# oscillograph.net
KiCad netlist of a schematic drawn in Altium Designer
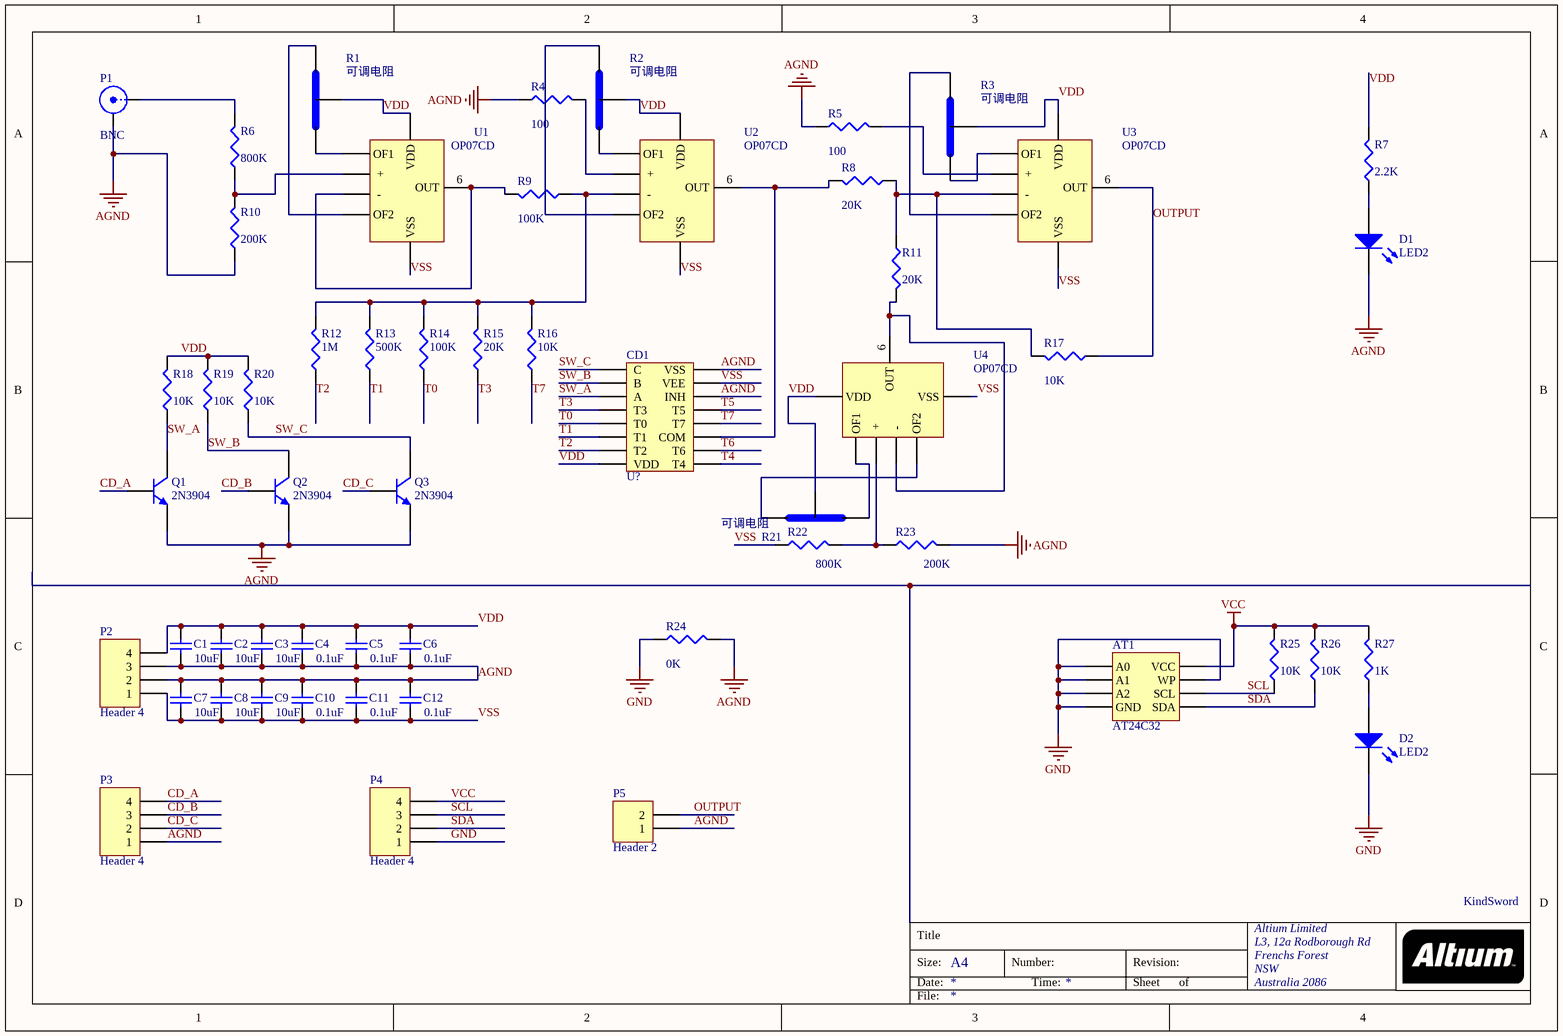
[diagram p0: oscillograph.SchDoc]

(export (version "E")
  (design (tool "Eeschema 10.0.6"))
  (components
    (comp (ref "AT1") (value "AT24C32") (footprint "AT24") (libsource (lib "AD元件库") (part "AT24C32")))
    (comp (ref "C1")
      (value "10uF")
      (footprint "1608[0603]")
      (description "Capacitor (Semiconductor SIM Model)")
      (fields (field (name "Comment") "Cap Semi") (field (name "PUBLISHER") "Altium Limited"))
      (libsource (lib "Miscellaneous Devices") (part "Cap Semi"))
    )
    (comp (ref "C2")
      (value "10uF")
      (footprint "1608[0603]")
      (description "Capacitor (Semiconductor SIM Model)")
      (fields (field (name "Comment") "Cap Semi") (field (name "PUBLISHER") "Altium Limited"))
      (libsource (lib "Miscellaneous Devices") (part "Cap Semi"))
    )
    (comp (ref "C3")
      (value "10uF")
      (footprint "1608[0603]")
      (description "Capacitor (Semiconductor SIM Model)")
      (fields (field (name "Comment") "Cap Semi") (field (name "PUBLISHER") "Altium Limited"))
      (libsource (lib "Miscellaneous Devices") (part "Cap Semi"))
    )
    (comp (ref "C4")
      (value "0.1uF")
      (footprint "1608[0603]")
      (description "Capacitor (Semiconductor SIM Model)")
      (fields (field (name "Comment") "Cap Semi") (field (name "PUBLISHER") "Altium Limited"))
      (libsource (lib "Miscellaneous Devices") (part "Cap Semi"))
    )
    (comp (ref "C5")
      (value "0.1uF")
      (footprint "1608[0603]")
      (description "Capacitor (Semiconductor SIM Model)")
      (fields (field (name "Comment") "Cap Semi") (field (name "PUBLISHER") "Altium Limited"))
      (libsource (lib "Miscellaneous Devices") (part "Cap Semi"))
    )
    (comp (ref "C6")
      (value "0.1uF")
      (footprint "1608[0603]")
      (description "Capacitor (Semiconductor SIM Model)")
      (fields (field (name "Comment") "Cap Semi") (field (name "PUBLISHER") "Altium Limited"))
      (libsource (lib "Miscellaneous Devices") (part "Cap Semi"))
    )
    (comp (ref "C7")
      (value "10uF")
      (footprint "1608[0603]")
      (description "Capacitor (Semiconductor SIM Model)")
      (fields (field (name "Comment") "Cap Semi") (field (name "PUBLISHER") "Altium Limited"))
      (libsource (lib "Miscellaneous Devices") (part "Cap Semi"))
    )
    (comp (ref "C8")
      (value "10uF")
      (footprint "1608[0603]")
      (description "Capacitor (Semiconductor SIM Model)")
      (fields (field (name "Comment") "Cap Semi") (field (name "PUBLISHER") "Altium Limited"))
      (libsource (lib "Miscellaneous Devices") (part "Cap Semi"))
    )
    (comp (ref "C9")
      (value "10uF")
      (footprint "1608[0603]")
      (description "Capacitor (Semiconductor SIM Model)")
      (fields (field (name "Comment") "Cap Semi") (field (name "PUBLISHER") "Altium Limited"))
      (libsource (lib "Miscellaneous Devices") (part "Cap Semi"))
    )
    (comp (ref "C10")
      (value "0.1uF")
      (footprint "1608[0603]")
      (description "Capacitor (Semiconductor SIM Model)")
      (fields (field (name "Comment") "Cap Semi") (field (name "PUBLISHER") "Altium Limited"))
      (libsource (lib "Miscellaneous Devices") (part "Cap Semi"))
    )
    (comp (ref "C11")
      (value "0.1uF")
      (footprint "1608[0603]")
      (description "Capacitor (Semiconductor SIM Model)")
      (fields (field (name "Comment") "Cap Semi") (field (name "PUBLISHER") "Altium Limited"))
      (libsource (lib "Miscellaneous Devices") (part "Cap Semi"))
    )
    (comp (ref "C12")
      (value "0.1uF")
      (footprint "1608[0603]")
      (description "Capacitor (Semiconductor SIM Model)")
      (fields (field (name "Comment") "Cap Semi") (field (name "PUBLISHER") "Altium Limited"))
      (libsource (lib "Miscellaneous Devices") (part "Cap Semi"))
    )
    (comp (ref "CD1")
      (value "U?")
      (footprint "cd4051")
      (description "CD4051")
      (libsource (lib "AD元件库") (part "CD4051B"))
    )
    (comp (ref "D1")
      (value "LED2")
      (footprint "3.2X1.6X1.1")
      (description "Typical RED, GREEN, YELLOW, AMBER GaAs LED")
      (fields (field (name "PUBLISHER") "Altium Limited"))
      (libsource (lib "Miscellaneous Devices") (part "LED2"))
    )
    (comp (ref "D2")
      (value "LED2")
      (footprint "3.2X1.6X1.1")
      (description "Typical RED, GREEN, YELLOW, AMBER GaAs LED")
      (fields (field (name "PUBLISHER") "Altium Limited"))
      (libsource (lib "Miscellaneous Devices") (part "LED2"))
    )
    (comp (ref "Logo1")
      (value "~")
      (footprint "logo")
      (description "L?")
      (libsource (lib "AD元件库") (part "logo"))
    )
    (comp (ref "P1")
      (value "BNC")
      (footprint "BNC_RA CON")
      (description "BNC Elbow Connector")
      (fields (field (name "PUBLISHER") "Altium Limited"))
      (libsource (lib "Miscellaneous Connectors") (part "BNC"))
    )
    (comp (ref "P2")
      (value "Header 4")
      (footprint "HDR1X4")
      (description "Header, 4-Pin")
      (fields (field (name "PUBLISHER") "Altium Limited"))
      (libsource (lib "Miscellaneous Connectors") (part "Header 4"))
    )
    (comp (ref "P3")
      (value "Header 4")
      (footprint "HDR1X4")
      (description "Header, 4-Pin")
      (fields (field (name "PUBLISHER") "Altium Limited"))
      (libsource (lib "Miscellaneous Connectors") (part "Header 4"))
    )
    (comp (ref "P4")
      (value "Header 4")
      (footprint "HDR1X4")
      (description "Header, 4-Pin")
      (fields (field (name "PUBLISHER") "Altium Limited"))
      (libsource (lib "Miscellaneous Connectors") (part "Header 4"))
    )
    (comp (ref "P5")
      (value "Header 2")
      (footprint "HDR1X2")
      (description "Header, 2-Pin")
      (fields (field (name "PUBLISHER") "Altium Limited"))
      (libsource (lib "Miscellaneous Connectors") (part "Header 2"))
    )
    (comp (ref "Q1")
      (value "2N3904")
      (footprint "TO-92A")
      (description "NPN General Purpose Amplifier")
      (fields (field (name "PUBLISHER") "Altium Limited"))
      (libsource (lib "Miscellaneous Devices") (part "2N3904"))
    )
    (comp (ref "Q2")
      (value "2N3904")
      (footprint "TO-92A")
      (description "NPN General Purpose Amplifier")
      (fields (field (name "PUBLISHER") "Altium Limited"))
      (libsource (lib "Miscellaneous Devices") (part "2N3904"))
    )
    (comp (ref "Q3")
      (value "2N3904")
      (footprint "TO-92A")
      (description "NPN General Purpose Amplifier")
      (fields (field (name "PUBLISHER") "Altium Limited"))
      (libsource (lib "Miscellaneous Devices") (part "2N3904"))
    )
    (comp (ref "R1")
      (value "可调电阻")
      (footprint "3296可调电阻")
      (description "R?")
      (libsource (lib "AD元件库") (part "3296可调电阻"))
    )
    (comp (ref "R2")
      (value "可调电阻")
      (footprint "3296可调电阻")
      (description "R?")
      (libsource (lib "AD元件库") (part "3296可调电阻"))
    )
    (comp (ref "R3")
      (value "可调电阻")
      (footprint "3296可调电阻")
      (description "R?")
      (libsource (lib "AD元件库") (part "3296可调电阻"))
    )
    (comp (ref "R4")
      (value "100")
      (footprint "J1-0603")
      (description "Resistor")
      (fields (field (name "Comment") "Res3") (field (name "PUBLISHER") "Altium Limited"))
      (libsource (lib "Miscellaneous Devices") (part "Res3"))
    )
    (comp (ref "R5")
      (value "100")
      (footprint "J1-0603")
      (description "Resistor")
      (fields (field (name "Comment") "Res3") (field (name "PUBLISHER") "Altium Limited"))
      (libsource (lib "Miscellaneous Devices") (part "Res3"))
    )
    (comp (ref "R6")
      (value "800K")
      (footprint "J1-0603")
      (description "Resistor")
      (fields (field (name "Comment") "Res3") (field (name "PUBLISHER") "Altium Limited"))
      (libsource (lib "Miscellaneous Devices") (part "Res3"))
    )
    (comp (ref "R7")
      (value "2.2K")
      (footprint "J1-0603")
      (description "Resistor")
      (fields (field (name "Comment") "Res3") (field (name "PUBLISHER") "Altium Limited"))
      (libsource (lib "Miscellaneous Devices") (part "Res3"))
    )
    (comp (ref "R8")
      (value "20K")
      (footprint "J1-0603")
      (description "Resistor")
      (fields (field (name "Comment") "Res3") (field (name "PUBLISHER") "Altium Limited"))
      (libsource (lib "Miscellaneous Devices") (part "Res3"))
    )
    (comp (ref "R9")
      (value "100K")
      (footprint "J1-0603")
      (description "Resistor")
      (fields (field (name "Comment") "Res3") (field (name "PUBLISHER") "Altium Limited"))
      (libsource (lib "Miscellaneous Devices") (part "Res3"))
    )
    (comp (ref "R10")
      (value "200K")
      (footprint "J1-0603")
      (description "Resistor")
      (fields (field (name "Comment") "Res3") (field (name "PUBLISHER") "Altium Limited"))
      (libsource (lib "Miscellaneous Devices") (part "Res3"))
    )
    (comp (ref "R11")
      (value "20K")
      (footprint "J1-0603")
      (description "Resistor")
      (fields (field (name "Comment") "Res3") (field (name "PUBLISHER") "Altium Limited"))
      (libsource (lib "Miscellaneous Devices") (part "Res3"))
    )
    (comp (ref "R12")
      (value "1M")
      (footprint "J1-0603")
      (description "Resistor")
      (fields (field (name "Comment") "Res3") (field (name "PUBLISHER") "Altium Limited"))
      (libsource (lib "Miscellaneous Devices") (part "Res3"))
    )
    (comp (ref "R13")
      (value "500K")
      (footprint "J1-0603")
      (description "Resistor")
      (fields (field (name "Comment") "Res3") (field (name "PUBLISHER") "Altium Limited"))
      (libsource (lib "Miscellaneous Devices") (part "Res3"))
    )
    (comp (ref "R14")
      (value "100K")
      (footprint "J1-0603")
      (description "Resistor")
      (fields (field (name "Comment") "Res3") (field (name "PUBLISHER") "Altium Limited"))
      (libsource (lib "Miscellaneous Devices") (part "Res3"))
    )
    (comp (ref "R15")
      (value "20K")
      (footprint "J1-0603")
      (description "Resistor")
      (fields (field (name "Comment") "Res3") (field (name "PUBLISHER") "Altium Limited"))
      (libsource (lib "Miscellaneous Devices") (part "Res3"))
    )
    (comp (ref "R16")
      (value "10K")
      (footprint "J1-0603")
      (description "Resistor")
      (fields (field (name "Comment") "Res3") (field (name "PUBLISHER") "Altium Limited"))
      (libsource (lib "Miscellaneous Devices") (part "Res3"))
    )
    (comp (ref "R17")
      (value "10K")
      (footprint "J1-0603")
      (description "Resistor")
      (fields (field (name "Comment") "Res3") (field (name "PUBLISHER") "Altium Limited"))
      (libsource (lib "Miscellaneous Devices") (part "Res3"))
    )
    (comp (ref "R18")
      (value "10K")
      (footprint "J1-0603")
      (description "Resistor")
      (fields (field (name "Comment") "Res3") (field (name "PUBLISHER") "Altium Limited"))
      (libsource (lib "Miscellaneous Devices") (part "Res3"))
    )
    (comp (ref "R19")
      (value "10K")
      (footprint "J1-0603")
      (description "Resistor")
      (fields (field (name "Comment") "Res3") (field (name "PUBLISHER") "Altium Limited"))
      (libsource (lib "Miscellaneous Devices") (part "Res3"))
    )
    (comp (ref "R20")
      (value "10K")
      (footprint "J1-0603")
      (description "Resistor")
      (fields (field (name "Comment") "Res3") (field (name "PUBLISHER") "Altium Limited"))
      (libsource (lib "Miscellaneous Devices") (part "Res3"))
    )
    (comp (ref "R21")
      (value "可调电阻")
      (footprint "3296可调电阻")
      (description "R?")
      (libsource (lib "AD元件库") (part "3296可调电阻"))
    )
    (comp (ref "R22")
      (value "800K")
      (footprint "J1-0603")
      (description "Resistor")
      (fields (field (name "Comment") "Res3") (field (name "PUBLISHER") "Altium Limited"))
      (libsource (lib "Miscellaneous Devices") (part "Res3"))
    )
    (comp (ref "R23")
      (value "200K")
      (footprint "J1-0603")
      (description "Resistor")
      (fields (field (name "Comment") "Res3") (field (name "PUBLISHER") "Altium Limited"))
      (libsource (lib "Miscellaneous Devices") (part "Res3"))
    )
    (comp (ref "R24")
      (value "0K")
      (footprint "J1-0603")
      (description "Resistor")
      (fields (field (name "Comment") "Res3") (field (name "PUBLISHER") "Altium Limited"))
      (libsource (lib "Miscellaneous Devices") (part "Res3"))
    )
    (comp (ref "R25")
      (value "10K")
      (footprint "J1-0603")
      (description "Resistor")
      (fields (field (name "Comment") "Res3") (field (name "PUBLISHER") "Altium Limited"))
      (libsource (lib "Miscellaneous Devices") (part "Res3"))
    )
    (comp (ref "R26")
      (value "10K")
      (footprint "J1-0603")
      (description "Resistor")
      (fields (field (name "Comment") "Res3") (field (name "PUBLISHER") "Altium Limited"))
      (libsource (lib "Miscellaneous Devices") (part "Res3"))
    )
    (comp (ref "R27")
      (value "1K")
      (footprint "J1-0603")
      (description "Resistor")
      (fields (field (name "Comment") "Res3") (field (name "PUBLISHER") "Altium Limited"))
      (libsource (lib "Miscellaneous Devices") (part "Res3"))
    )
    (comp (ref "U1") (value "OP07CD") (footprint "OP07C") (libsource (lib "AD元件库") (part "OP07CD")))
    (comp (ref "U2") (value "OP07CD") (footprint "OP07C") (libsource (lib "AD元件库") (part "OP07CD")))
    (comp (ref "U3") (value "OP07CD") (footprint "OP07C") (libsource (lib "AD元件库") (part "OP07CD")))
    (comp (ref "U4") (value "OP07CD") (footprint "OP07C") (libsource (lib "") (part "OP07CD_1")))
  )
  (nets
    (net (code "1") (name "/CD_A") (class "Default")
      (node (ref "P3") (pin "4") (pinfunction "4_4") (pintype "passive"))
      (node (ref "Q1") (pin "2") (pinfunction "B_2") (pintype "passive"))
    )
    (net (code "2") (name "/CD_B") (class "Default")
      (node (ref "P3") (pin "3") (pinfunction "3_3") (pintype "passive"))
      (node (ref "Q2") (pin "2") (pinfunction "B_2") (pintype "passive"))
    )
    (net (code "3") (name "/CD_C") (class "Default")
      (node (ref "P3") (pin "2") (pinfunction "2_2") (pintype "passive"))
      (node (ref "Q3") (pin "2") (pinfunction "B_2") (pintype "passive"))
    )
    (net (code "4") (name "/OUTPUT") (class "Default")
      (node (ref "P5") (pin "2") (pinfunction "2_2") (pintype "passive"))
      (node (ref "R17") (pin "1") (pinfunction "1_1") (pintype "passive"))
      (node (ref "U3") (pin "6") (pinfunction "OUT_6") (pintype "passive"))
    )
    (net (code "5") (name "/SCL") (class "Default")
      (node (ref "AT1") (pin "6") (pinfunction "SCL_6") (pintype "passive"))
      (node (ref "P4") (pin "3") (pinfunction "3_3") (pintype "passive"))
      (node (ref "R25") (pin "1") (pinfunction "1_1") (pintype "passive"))
    )
    (net (code "6") (name "/SDA") (class "Default")
      (node (ref "AT1") (pin "5") (pinfunction "SDA_5") (pintype "passive"))
      (node (ref "P4") (pin "2") (pinfunction "2_2") (pintype "passive"))
      (node (ref "R26") (pin "1") (pinfunction "1_1") (pintype "passive"))
    )
    (net (code "7") (name "/SW_A") (class "Default")
      (node (ref "CD1") (pin "11") (pinfunction "A_11") (pintype "passive"))
      (node (ref "Q1") (pin "3") (pinfunction "C_3") (pintype "passive"))
      (node (ref "R18") (pin "1") (pinfunction "1_1") (pintype "passive"))
    )
    (net (code "8") (name "/SW_B") (class "Default")
      (node (ref "CD1") (pin "10") (pinfunction "B_10") (pintype "passive"))
      (node (ref "Q2") (pin "3") (pinfunction "C_3") (pintype "passive"))
      (node (ref "R19") (pin "1") (pinfunction "1_1") (pintype "passive"))
    )
    (net (code "9") (name "/SW_C") (class "Default")
      (node (ref "CD1") (pin "9") (pinfunction "C_9") (pintype "passive"))
      (node (ref "Q3") (pin "3") (pinfunction "C_3") (pintype "passive"))
      (node (ref "R20") (pin "1") (pinfunction "1_1") (pintype "passive"))
    )
    (net (code "10") (name "/T0") (class "Default")
      (node (ref "CD1") (pin "13") (pinfunction "T0_13") (pintype "passive"))
      (node (ref "R14") (pin "1") (pinfunction "1_1") (pintype "passive"))
    )
    (net (code "11") (name "/T1") (class "Default")
      (node (ref "CD1") (pin "14") (pinfunction "T1_14") (pintype "passive"))
      (node (ref "R13") (pin "1") (pinfunction "1_1") (pintype "passive"))
    )
    (net (code "12") (name "/T2") (class "Default")
      (node (ref "CD1") (pin "15") (pinfunction "T2_15") (pintype "passive"))
      (node (ref "R12") (pin "1") (pinfunction "1_1") (pintype "passive"))
    )
    (net (code "13") (name "/T3") (class "Default")
      (node (ref "CD1") (pin "12") (pinfunction "T3_12") (pintype "passive"))
      (node (ref "R15") (pin "1") (pinfunction "1_1") (pintype "passive"))
    )
    (net (code "14") (name "/T4") (class "Default")
      (node (ref "CD1") (pin "1") (pinfunction "T4_1") (pintype "passive"))
    )
    (net (code "15") (name "/T5") (class "Default")
      (node (ref "CD1") (pin "5") (pinfunction "T5_5") (pintype "passive"))
    )
    (net (code "16") (name "/T6") (class "Default")
      (node (ref "CD1") (pin "2") (pinfunction "T6_2") (pintype "passive"))
    )
    (net (code "17") (name "/T7") (class "Default")
      (node (ref "CD1") (pin "4") (pinfunction "T7_4") (pintype "passive"))
      (node (ref "R16") (pin "1") (pinfunction "1_1") (pintype "passive"))
    )
    (net (code "18") (name "/VDD") (class "Default")
      (node (ref "C1") (pin "2") (pinfunction "2_2") (pintype "passive"))
      (node (ref "C2") (pin "2") (pinfunction "2_2") (pintype "passive"))
      (node (ref "C3") (pin "2") (pinfunction "2_2") (pintype "passive"))
      (node (ref "C4") (pin "2") (pinfunction "2_2") (pintype "passive"))
      (node (ref "C5") (pin "2") (pinfunction "2_2") (pintype "passive"))
      (node (ref "C6") (pin "2") (pinfunction "2_2") (pintype "passive"))
      (node (ref "CD1") (pin "16") (pinfunction "VDD_16") (pintype "passive"))
      (node (ref "P2") (pin "4") (pinfunction "4_4") (pintype "passive"))
      (node (ref "R1") (pin "1") (pinfunction "4_1") (pintype "passive"))
      (node (ref "R18") (pin "2") (pinfunction "2_2") (pintype "passive"))
      (node (ref "R19") (pin "2") (pinfunction "2_2") (pintype "passive"))
      (node (ref "R2") (pin "1") (pinfunction "4_1") (pintype "passive"))
      (node (ref "R20") (pin "2") (pinfunction "2_2") (pintype "passive"))
      (node (ref "R21") (pin "1") (pinfunction "4_1") (pintype "passive"))
      (node (ref "R3") (pin "1") (pinfunction "4_1") (pintype "passive"))
      (node (ref "R7") (pin "2") (pinfunction "2_2") (pintype "passive"))
      (node (ref "U1") (pin "7") (pinfunction "VDD_7") (pintype "passive"))
      (node (ref "U2") (pin "7") (pinfunction "VDD_7") (pintype "passive"))
      (node (ref "U3") (pin "7") (pinfunction "VDD_7") (pintype "passive"))
      (node (ref "U4") (pin "7") (pinfunction "VDD_7") (pintype "passive"))
    )
    (net (code "19") (name "/VSS") (class "Default")
      (node (ref "C10") (pin "1") (pinfunction "1_1") (pintype "passive"))
      (node (ref "C11") (pin "1") (pinfunction "1_1") (pintype "passive"))
      (node (ref "C12") (pin "1") (pinfunction "1_1") (pintype "passive"))
      (node (ref "C7") (pin "1") (pinfunction "1_1") (pintype "passive"))
      (node (ref "C8") (pin "1") (pinfunction "1_1") (pintype "passive"))
      (node (ref "C9") (pin "1") (pinfunction "1_1") (pintype "passive"))
      (node (ref "CD1") (pin "7") (pinfunction "VEE_7") (pintype "passive"))
      (node (ref "P2") (pin "1") (pinfunction "1_1") (pintype "passive"))
      (node (ref "R22") (pin "1") (pinfunction "1_1") (pintype "passive"))
      (node (ref "U1") (pin "4") (pinfunction "VSS_4") (pintype "passive"))
      (node (ref "U2") (pin "4") (pinfunction "VSS_4") (pintype "passive"))
      (node (ref "U3") (pin "4") (pinfunction "VSS_4") (pintype "passive"))
      (node (ref "U4") (pin "4") (pinfunction "VSS_4") (pintype "passive"))
    )
    (net (code "20") (name "AGND") (class "Default")
      (node (ref "C1") (pin "1") (pinfunction "1_1") (pintype "passive"))
      (node (ref "C10") (pin "2") (pinfunction "2_2") (pintype "passive"))
      (node (ref "C11") (pin "2") (pinfunction "2_2") (pintype "passive"))
      (node (ref "C12") (pin "2") (pinfunction "2_2") (pintype "passive"))
      (node (ref "C2") (pin "1") (pinfunction "1_1") (pintype "passive"))
      (node (ref "C3") (pin "1") (pinfunction "1_1") (pintype "passive"))
      (node (ref "C4") (pin "1") (pinfunction "1_1") (pintype "passive"))
      (node (ref "C5") (pin "1") (pinfunction "1_1") (pintype "passive"))
      (node (ref "C6") (pin "1") (pinfunction "1_1") (pintype "passive"))
      (node (ref "C7") (pin "2") (pinfunction "2_2") (pintype "passive"))
      (node (ref "C8") (pin "2") (pinfunction "2_2") (pintype "passive"))
      (node (ref "C9") (pin "2") (pinfunction "2_2") (pintype "passive"))
      (node (ref "CD1") (pin "6") (pinfunction "INH_6") (pintype "passive"))
      (node (ref "CD1") (pin "8") (pinfunction "VSS_8") (pintype "passive"))
      (node (ref "D1") (pin "2") (pinfunction "K_2") (pintype "passive"))
      (node (ref "P1") (pin "2") (pinfunction "Y_2") (pintype "passive"))
      (node (ref "P2") (pin "2") (pinfunction "2_2") (pintype "passive"))
      (node (ref "P2") (pin "3") (pinfunction "3_3") (pintype "passive"))
      (node (ref "P3") (pin "1") (pinfunction "1_1") (pintype "passive"))
      (node (ref "P5") (pin "1") (pinfunction "1_1") (pintype "passive"))
      (node (ref "Q1") (pin "1") (pinfunction "E_1") (pintype "passive"))
      (node (ref "Q2") (pin "1") (pinfunction "E_1") (pintype "passive"))
      (node (ref "Q3") (pin "1") (pinfunction "E_1") (pintype "passive"))
      (node (ref "R10") (pin "1") (pinfunction "1_1") (pintype "passive"))
      (node (ref "R23") (pin "2") (pinfunction "2_2") (pintype "passive"))
      (node (ref "R24") (pin "2") (pinfunction "2_2") (pintype "passive"))
      (node (ref "R4") (pin "1") (pinfunction "1_1") (pintype "passive"))
      (node (ref "R5") (pin "1") (pinfunction "1_1") (pintype "passive"))
    )
    (net (code "21") (name "GND") (class "Default")
      (node (ref "AT1") (pin "1") (pinfunction "A0_1") (pintype "passive"))
      (node (ref "AT1") (pin "2") (pinfunction "A1_2") (pintype "passive"))
      (node (ref "AT1") (pin "3") (pinfunction "A2_3") (pintype "passive"))
      (node (ref "AT1") (pin "4") (pinfunction "GND_4") (pintype "passive"))
      (node (ref "AT1") (pin "7") (pinfunction "WP_7") (pintype "passive"))
      (node (ref "D2") (pin "2") (pinfunction "K_2") (pintype "passive"))
      (node (ref "P4") (pin "1") (pinfunction "1_1") (pintype "passive"))
      (node (ref "R24") (pin "1") (pinfunction "1_1") (pintype "passive"))
    )
    (net (code "22") (name "Net-(CD1-COM)") (class "Default")
      (node (ref "CD1") (pin "3") (pinfunction "COM_3") (pintype "passive"))
      (node (ref "R8") (pin "2") (pinfunction "2_2") (pintype "passive"))
      (node (ref "U2") (pin "6") (pinfunction "OUT_6") (pintype "passive"))
    )
    (net (code "23") (name "Net-(D1-A)") (class "Default")
      (node (ref "D1") (pin "1") (pinfunction "A_1") (pintype "passive"))
      (node (ref "R7") (pin "1") (pinfunction "1_1") (pintype "passive"))
    )
    (net (code "24") (name "Net-(D2-A)") (class "Default")
      (node (ref "D2") (pin "1") (pinfunction "A_1") (pintype "passive"))
      (node (ref "R27") (pin "1") (pinfunction "1_1") (pintype "passive"))
    )
    (net (code "25") (name "Net-(P1-X)") (class "Default")
      (node (ref "P1") (pin "1") (pinfunction "X_1") (pintype "passive"))
      (node (ref "R6") (pin "2") (pinfunction "2_2") (pintype "passive"))
    )
    (net (code "26") (name "Net-(R1-1)") (class "Default")
      (node (ref "R1") (pin "0") (pinfunction "1_0") (pintype "passive"))
      (node (ref "U1") (pin "8") (pinfunction "OF2_8") (pintype "passive"))
    )
    (net (code "27") (name "Net-(R1-14)") (class "Default")
      (node (ref "R1") (pin "2") (pinfunction "14_2") (pintype "passive"))
      (node (ref "U1") (pin "1") (pinfunction "OF1_1") (pintype "passive"))
    )
    (net (code "28") (name "Net-(R2-1)") (class "Default")
      (node (ref "R2") (pin "0") (pinfunction "1_0") (pintype "passive"))
      (node (ref "U2") (pin "8") (pinfunction "OF2_8") (pintype "passive"))
    )
    (net (code "29") (name "Net-(R2-14)") (class "Default")
      (node (ref "R2") (pin "2") (pinfunction "14_2") (pintype "passive"))
      (node (ref "U2") (pin "1") (pinfunction "OF1_1") (pintype "passive"))
    )
    (net (code "30") (name "Net-(R3-1)") (class "Default")
      (node (ref "R3") (pin "0") (pinfunction "1_0") (pintype "passive"))
      (node (ref "U3") (pin "8") (pinfunction "OF2_8") (pintype "passive"))
    )
    (net (code "31") (name "Net-(R3-14)") (class "Default")
      (node (ref "R3") (pin "2") (pinfunction "14_2") (pintype "passive"))
      (node (ref "U3") (pin "1") (pinfunction "OF1_1") (pintype "passive"))
    )
    (net (code "32") (name "Net-(R21-1)") (class "Default")
      (node (ref "R21") (pin "0") (pinfunction "1_0") (pintype "passive"))
      (node (ref "U4") (pin "8") (pinfunction "OF2_8") (pintype "passive"))
    )
    (net (code "33") (name "Net-(R21-14)") (class "Default")
      (node (ref "R21") (pin "2") (pinfunction "14_2") (pintype "passive"))
      (node (ref "U4") (pin "1") (pinfunction "OF1_1") (pintype "passive"))
    )
    (net (code "34") (name "Net-(U1-+)") (class "Default")
      (node (ref "R10") (pin "2") (pinfunction "2_2") (pintype "passive"))
      (node (ref "R6") (pin "1") (pinfunction "1_1") (pintype "passive"))
      (node (ref "U1") (pin "3") (pinfunction "+_3") (pintype "passive"))
    )
    (net (code "35") (name "Net-(U1--)") (class "Default")
      (node (ref "R9") (pin "2") (pinfunction "2_2") (pintype "passive"))
      (node (ref "U1") (pin "2") (pinfunction "-_2") (pintype "passive"))
      (node (ref "U1") (pin "6") (pinfunction "OUT_6") (pintype "passive"))
    )
    (net (code "36") (name "Net-(U2-+)") (class "Default")
      (node (ref "R4") (pin "2") (pinfunction "2_2") (pintype "passive"))
      (node (ref "U2") (pin "3") (pinfunction "+_3") (pintype "passive"))
    )
    (net (code "37") (name "Net-(U2--)") (class "Default")
      (node (ref "R12") (pin "2") (pinfunction "2_2") (pintype "passive"))
      (node (ref "R13") (pin "2") (pinfunction "2_2") (pintype "passive"))
      (node (ref "R14") (pin "2") (pinfunction "2_2") (pintype "passive"))
      (node (ref "R15") (pin "2") (pinfunction "2_2") (pintype "passive"))
      (node (ref "R16") (pin "2") (pinfunction "2_2") (pintype "passive"))
      (node (ref "R9") (pin "1") (pinfunction "1_1") (pintype "passive"))
      (node (ref "U2") (pin "2") (pinfunction "-_2") (pintype "passive"))
    )
    (net (code "38") (name "Net-(U3-+)") (class "Default")
      (node (ref "R5") (pin "2") (pinfunction "2_2") (pintype "passive"))
      (node (ref "U3") (pin "3") (pinfunction "+_3") (pintype "passive"))
    )
    (net (code "39") (name "Net-(U3--)") (class "Default")
      (node (ref "R11") (pin "1") (pinfunction "1_1") (pintype "passive"))
      (node (ref "R17") (pin "2") (pinfunction "2_2") (pintype "passive"))
      (node (ref "R8") (pin "1") (pinfunction "1_1") (pintype "passive"))
      (node (ref "U3") (pin "2") (pinfunction "-_2") (pintype "passive"))
    )
    (net (code "40") (name "Net-(U4-+)") (class "Default")
      (node (ref "R22") (pin "2") (pinfunction "2_2") (pintype "passive"))
      (node (ref "R23") (pin "1") (pinfunction "1_1") (pintype "passive"))
      (node (ref "U4") (pin "3") (pinfunction "+_3") (pintype "passive"))
    )
    (net (code "41") (name "Net-(U4--)") (class "Default")
      (node (ref "R11") (pin "2") (pinfunction "2_2") (pintype "passive"))
      (node (ref "U4") (pin "2") (pinfunction "-_2") (pintype "passive"))
      (node (ref "U4") (pin "6") (pinfunction "OUT_6") (pintype "passive"))
    )
    (net (code "42") (name "VCC") (class "Default")
      (node (ref "AT1") (pin "8") (pinfunction "VCC_8") (pintype "passive"))
      (node (ref "P4") (pin "4") (pinfunction "4_4") (pintype "passive"))
      (node (ref "R25") (pin "2") (pinfunction "2_2") (pintype "passive"))
      (node (ref "R26") (pin "2") (pinfunction "2_2") (pintype "passive"))
      (node (ref "R27") (pin "2") (pinfunction "2_2") (pintype "passive"))
    )
  )
)
